# filtroFinal-TC.net
KiCad netlist of a schematic drawn in Altium Designer
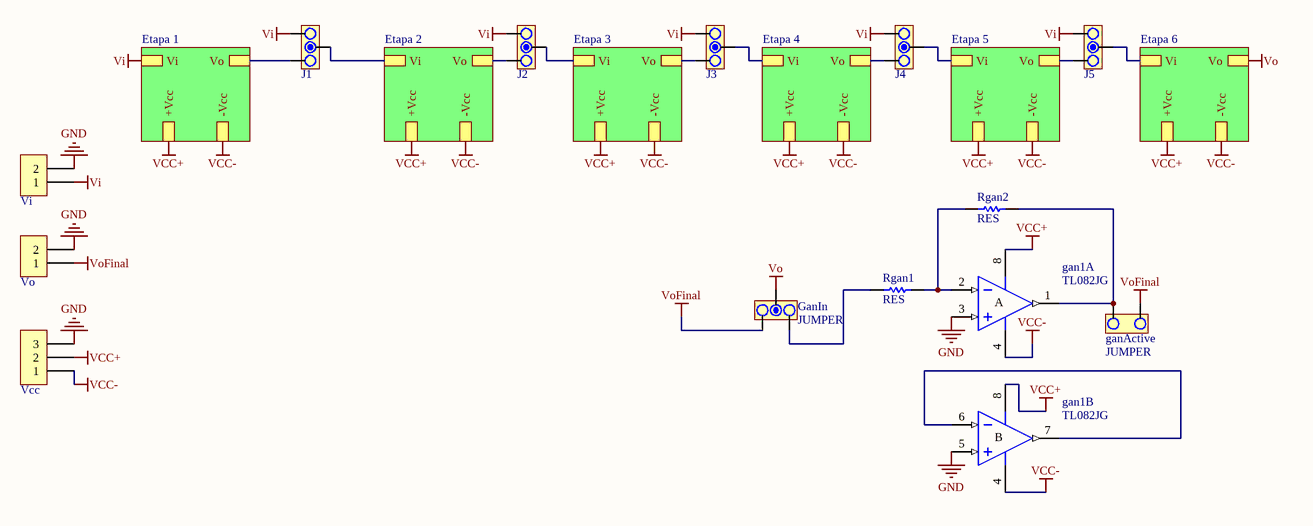
[diagram p0: filtroFinal-TC.SchDoc]

(export (version "E")
  (design (tool "Eeschema 10.0.6"))
  (components
    (comp (ref "gan1")
      (value "TL082JG")
      (footprint "JG008")
      (description "JFET-Input Operational Amplifier")
      (fields (field (name "PUBLISHER") "Altium Limited"))
      (libsource (lib "TI Operational Amplifier") (part "TL082JG"))
    )
    (comp (ref "ganActive")
      (value "JUMPER")
      (footprint "JUMPER2")
      (libsource (lib "LIBEBAL") (part "JUMPER"))
    )
    (comp (ref "GanIn") (value "JUMPER") (footprint "JUMPER3") (libsource (lib "") (part "JUMPER3_1")))
    (comp (ref "J1") (value "JUMPER") (footprint "JUMPER3") (libsource (lib "LIBEBAL") (part "JUMPER3")))
    (comp (ref "J2") (value "JUMPER") (footprint "JUMPER3") (libsource (lib "LIBEBAL") (part "JUMPER3")))
    (comp (ref "J3") (value "JUMPER") (footprint "JUMPER3") (libsource (lib "LIBEBAL") (part "JUMPER3")))
    (comp (ref "J4") (value "JUMPER") (footprint "JUMPER3") (libsource (lib "LIBEBAL") (part "JUMPER3")))
    (comp (ref "J5") (value "JUMPER") (footprint "JUMPER3") (libsource (lib "LIBEBAL") (part "JUMPER3")))
    (comp (ref "Rgan1") (value "RES") (footprint "RES300") (libsource (lib "LIBEBAL") (part "RES")))
    (comp (ref "Rgan2") (value "RES") (footprint "RES300") (libsource (lib "LIBEBAL") (part "RES")))
    (comp (ref "Vcc")
      (value "BORNERA 3")
      (footprint "BORNERA3")
      (libsource (lib "LIBEBAL") (part "BORNERA 3"))
    )
    (comp (ref "Vi")
      (value "BORNERA 2")
      (footprint "BORNERA2")
      (libsource (lib "LIBEBAL") (part "BORNERA 2"))
    )
    (comp (ref "Vo")
      (value "BORNERA 2")
      (footprint "BORNERA2")
      (libsource (lib "LIBEBAL") (part "BORNERA 2"))
    )
  )
  (nets
    (net (code "1") (name "/Vi") (class "Default")
      (node (ref "J5") (pin "2") (pinfunction "2_2") (pintype "passive"))
    )
    (net (code "2") (name "/Vi_1") (class "Default")
      (node (ref "J2") (pin "2") (pinfunction "2_2") (pintype "passive"))
    )
    (net (code "3") (name "/Vi_2") (class "Default")
      (node (ref "J1") (pin "2") (pinfunction "2_2") (pintype "passive"))
    )
    (net (code "4") (name "/Vi_3") (class "Default")
      (node (ref "J3") (pin "2") (pinfunction "2_2") (pintype "passive"))
    )
    (net (code "5") (name "/Vi_4") (class "Default")
      (node (ref "J4") (pin "2") (pinfunction "2_2") (pintype "passive"))
    )
    (net (code "6") (name "/Vo") (class "Default")
      (node (ref "J3") (pin "1") (pinfunction "1_1") (pintype "passive"))
    )
    (net (code "7") (name "/Vo_1") (class "Default")
      (node (ref "J2") (pin "1") (pinfunction "1_1") (pintype "passive"))
    )
    (net (code "8") (name "/Vo_2") (class "Default")
      (node (ref "J1") (pin "1") (pinfunction "1_1") (pintype "passive"))
    )
    (net (code "9") (name "/Vo_3") (class "Default")
      (node (ref "J4") (pin "1") (pinfunction "1_1") (pintype "passive"))
    )
    (net (code "10") (name "/Vo_4") (class "Default")
      (node (ref "J5") (pin "1") (pinfunction "1_1") (pintype "passive"))
    )
    (net (code "11") (name "GND") (class "Default")
      (node (ref "Vcc") (pin "3") (pinfunction "3_3") (pintype "passive"))
      (node (ref "Vi") (pin "2") (pinfunction "2_2") (pintype "passive"))
      (node (ref "Vo") (pin "2") (pinfunction "2_2") (pintype "passive"))
      (node (ref "gan1") (pin "3") (pinfunction "IN+_3") (pintype "input"))
      (node (ref "gan1") (pin "5") (pinfunction "IN+_5") (pintype "input"))
    )
    (net (code "12") (name "Net-(GanIn-Pad1)") (class "Default")
      (node (ref "GanIn") (pin "1") (pinfunction "1_1") (pintype "passive"))
      (node (ref "Rgan1") (pin "1") (pinfunction "1_1") (pintype "passive"))
    )
    (net (code "13") (name "Net-(gan1A-IN-)") (class "Default")
      (node (ref "Rgan1") (pin "2") (pinfunction "2_2") (pintype "passive"))
      (node (ref "Rgan2") (pin "1") (pinfunction "1_1") (pintype "passive"))
      (node (ref "gan1") (pin "2") (pinfunction "IN-_2") (pintype "input"))
    )
    (net (code "14") (name "Net-(gan1A-OUT)") (class "Default")
      (node (ref "Rgan2") (pin "2") (pinfunction "2_2") (pintype "passive"))
      (node (ref "gan1") (pin "1") (pinfunction "OUT_1") (pintype "output"))
      (node (ref "ganActive") (pin "1") (pinfunction "1_1") (pintype "passive"))
    )
    (net (code "15") (name "Net-(gan1B-IN-)") (class "Default")
      (node (ref "gan1") (pin "6") (pinfunction "IN-_6") (pintype "input"))
      (node (ref "gan1") (pin "7") (pinfunction "OUT_7") (pintype "output"))
    )
    (net (code "16") (name "VCC+") (class "Default")
      (node (ref "Vcc") (pin "2") (pinfunction "2_2") (pintype "passive"))
      (node (ref "gan1") (pin "8") (pinfunction "V+_8") (pintype "power_in"))
    )
    (net (code "17") (name "VCC-") (class "Default")
      (node (ref "Vcc") (pin "1") (pinfunction "1_1") (pintype "passive"))
      (node (ref "gan1") (pin "4") (pinfunction "V-_4") (pintype "power_in"))
    )
    (net (code "18") (name "Vi") (class "Default")
      (node (ref "J1") (pin "3") (pinfunction "3_3") (pintype "passive"))
      (node (ref "J2") (pin "3") (pinfunction "3_3") (pintype "passive"))
      (node (ref "J3") (pin "3") (pinfunction "3_3") (pintype "passive"))
      (node (ref "J4") (pin "3") (pinfunction "3_3") (pintype "passive"))
      (node (ref "J5") (pin "3") (pinfunction "3_3") (pintype "passive"))
      (node (ref "Vi") (pin "1") (pinfunction "1_1") (pintype "passive"))
    )
    (net (code "19") (name "Vo") (class "Default")
      (node (ref "GanIn") (pin "2") (pinfunction "2_2") (pintype "passive"))
    )
    (net (code "20") (name "VoFinal") (class "Default")
      (node (ref "GanIn") (pin "3") (pinfunction "3_3") (pintype "passive"))
      (node (ref "Vo") (pin "1") (pinfunction "1_1") (pintype "passive"))
      (node (ref "ganActive") (pin "2") (pinfunction "2_2") (pintype "passive"))
    )
  )
)
